# Top.net
KiCad netlist of a schematic drawn in Altium Designer
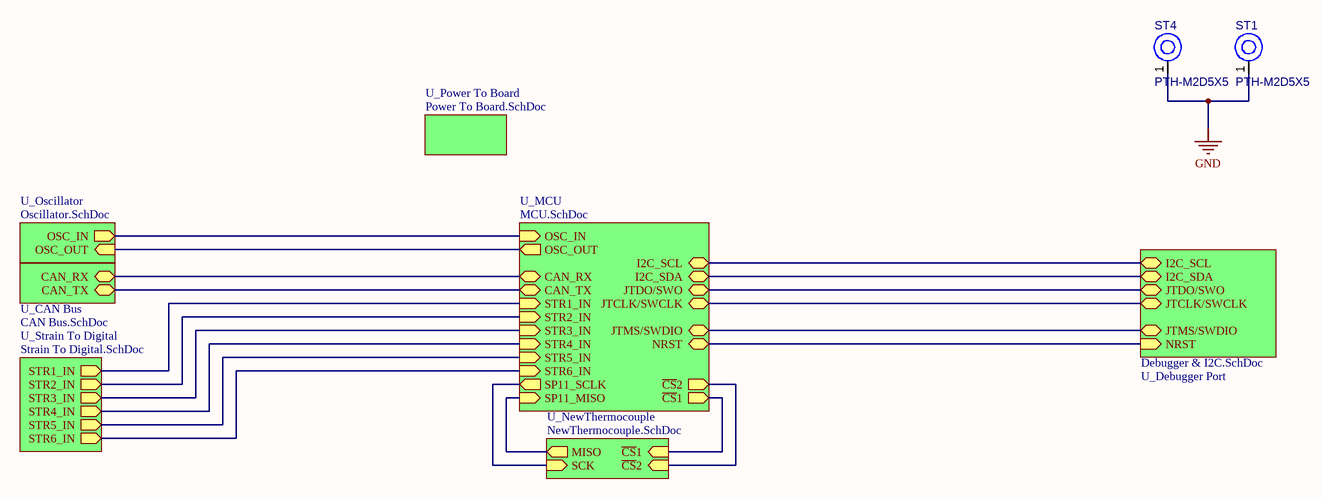
[diagram p0: Top.SchDoc]

(export (version "E")
  (design (tool "Eeschema 10.0.6"))
  (components
    (comp (ref "ST1")
      (value "PTH-M2D5X5")
      (footprint "PTH-M2D5X5")
      (description "M2 PTH (2.5mm), 5mm pad")
      (libsource (lib "Centaurus Racing Team") (part "CMP-00028-00000-1"))
    )
    (comp (ref "ST4")
      (value "PTH-M2D5X5")
      (footprint "PTH-M2D5X5")
      (description "M2 PTH (2.5mm), 5mm pad")
      (libsource (lib "Centaurus Racing Team") (part "CMP-00028-00000-1"))
    )
  )
  (nets
    (net (code "21") (name "GND") (class "Default")
      (node (ref "ST1") (pin "1") (pinfunction "H1_1") (pintype "passive"))
      (node (ref "ST4") (pin "1") (pinfunction "H1_1") (pintype "passive"))
    )
  )
)
